# UART-FTDI-USB.net
KiCad netlist of a schematic drawn in Altium Designer
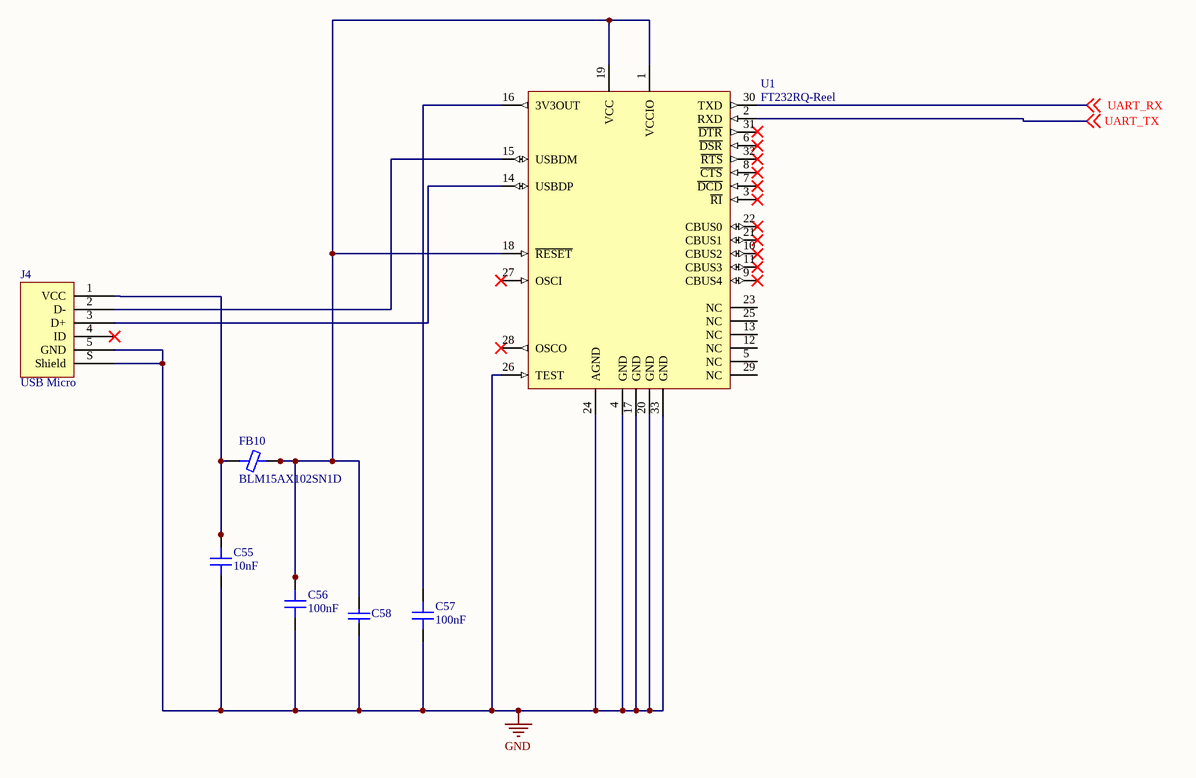
[diagram p0: UART-FTDI-USB.SchDoc]

(export (version "E")
  (design (tool "Eeschema 10.0.6"))
  (components
    (comp (ref "C55")
      (value "10nF")
      (footprint "CAP 0402/1005")
      (description "TAIYO YUDEN - TMK105B7103KV-F - CERAMIC CAPACITOR 0.01UF, 25V, X7R, 10%, 0402, FULL REEL")
      (fields (field (name "TOLERANCE") "10%") (field (name "VOLTAGE") "25V"))
      (libsource (lib "SCH - PASSIVES - CAPACITOR") (part "Capacitor"))
    )
    (comp (ref "C56")
      (value "100nF")
      (footprint "CAP 0402/1005")
      (description "Cap Ceramic 0.1uF 10V X5R 20% Pad SMD 0402 85C T/R")
      (fields (field (name "TOLERANCE") "20%"))
      (libsource (lib "SCH - PASSIVES - CAPACITOR") (part "Capacitor"))
    )
    (comp (ref "C57")
      (value "100nF")
      (footprint "CAP 0402/1005")
      (description "Cap Ceramic 0.1uF 10V X5R 20% Pad SMD 0402 85C T/R")
      (fields (field (name "TOLERANCE") "20%"))
      (libsource (lib "SCH - PASSIVES - CAPACITOR") (part "Capacitor"))
    )
    (comp (ref "C58")
      (value "GRM155R60J475ME47D")
      (footprint "CAPC1005X55X25NL05T10")
      (fields (field (name "MANUFACTURER") "Murata"))
      (libsource (lib "Altium Content Vault") (part "CAP"))
    )
    (comp (ref "FB10")
      (value "BLM15AX102SN1D")
      (footprint "FER 0402/1005")
      (description "Ferrite Beads Multi-Layer 1KOhm 25% 100MHz 350mA 490mOhm DCR 0402 T/R")
      (fields (field (name "TOLERANCE") "25%"))
      (libsource (lib "SCH - PASSIVES - FERRITE CHIP") (part "Ferrite Chip"))
    )
    (comp (ref "J4")
      (value "USB Micro")
      (footprint "FCI USB 10118193-0001LF")
      (description "CONN RCPT USB2.0 MICRO B SMD R/A")
      (libsource (lib "SCH - CONNECTORS - USB 2.0 TYPE B MICRO") (part "USB 2.0 Type B Micro"))
    )
    (comp (ref "U1")
      (value "FT232RQ-Reel")
      (footprint "PQFN5X5-32_V")
      (description "USB UART Asynchronous Serial Data Transfer Chip, 32-pin QFN, Tape and Reel")
      (fields (field (name "MANUFACTURER") "FTDI"))
      (libsource (lib "Altium Content Vault") (part "COM-UART-FT232R-SQ32"))
    )
  )
  (nets
    (net (code "1") (name "GND") (class "Default")
      (node (ref "C55") (pin "1") (pinfunction "1_1") (pintype "passive"))
      (node (ref "C56") (pin "1") (pinfunction "1_1") (pintype "passive"))
      (node (ref "C57") (pin "1") (pinfunction "1_1") (pintype "passive"))
      (node (ref "C58") (pin "1") (pinfunction "1_1") (pintype "passive"))
      (node (ref "J4") (pin "5") (pinfunction "GND_5") (pintype "passive"))
      (node (ref "J4") (pin "S") (pinfunction "Shield_S") (pintype "passive"))
      (node (ref "U1") (pin "17") (pinfunction "GND_17") (pintype "power_in"))
      (node (ref "U1") (pin "20") (pinfunction "GND_20") (pintype "power_in"))
      (node (ref "U1") (pin "24") (pinfunction "AGND_24") (pintype "power_in"))
      (node (ref "U1") (pin "26") (pinfunction "TEST_26") (pintype "input"))
      (node (ref "U1") (pin "33") (pinfunction "GND_33") (pintype "power_in"))
      (node (ref "U1") (pin "4") (pinfunction "GND_4") (pintype "power_in"))
    )
    (net (code "2") (name "Net-(J4-D+)") (class "Default")
      (node (ref "J4") (pin "3") (pinfunction "D+_3") (pintype "passive"))
      (node (ref "U1") (pin "14") (pinfunction "USBDP_14") (pintype "bidirectional"))
    )
    (net (code "3") (name "Net-(J4-D-)") (class "Default")
      (node (ref "J4") (pin "2") (pinfunction "D-_2") (pintype "passive"))
      (node (ref "U1") (pin "15") (pinfunction "USBDM_15") (pintype "bidirectional"))
    )
    (net (code "4") (name "Net-(J4-VCC)") (class "Default")
      (node (ref "C55") (pin "2") (pinfunction "2_2") (pintype "passive"))
      (node (ref "FB10") (pin "2") (pinfunction "2_2") (pintype "passive"))
      (node (ref "J4") (pin "1") (pinfunction "VCC_1") (pintype "passive"))
    )
    (net (code "5") (name "Net-(U1-3V3OUT)") (class "Default")
      (node (ref "C57") (pin "2") (pinfunction "2_2") (pintype "passive"))
      (node (ref "U1") (pin "16") (pinfunction "3V3OUT_16") (pintype "output"))
    )
    (net (code "6") (name "Net-(U1-VCC)") (class "Default")
      (node (ref "C56") (pin "2") (pinfunction "2_2") (pintype "passive"))
      (node (ref "C58") (pin "2") (pinfunction "2_2") (pintype "passive"))
      (node (ref "FB10") (pin "1") (pinfunction "1_1") (pintype "passive"))
      (node (ref "U1") (pin "1") (pinfunction "VCCIO_1") (pintype "power_in"))
      (node (ref "U1") (pin "18") (pinfunction "~{RESET}_18") (pintype "input"))
      (node (ref "U1") (pin "19") (pinfunction "VCC_19") (pintype "power_in"))
    )
    (net (code "7") (name "UART_RX") (class "Default")
      (node (ref "U1") (pin "30") (pinfunction "TXD_30") (pintype "output"))
    )
    (net (code "8") (name "UART_TX") (class "Default")
      (node (ref "U1") (pin "2") (pinfunction "RXD_2") (pintype "input"))
    )
    (net (code "9") (name "unconnected-(J4-ID-Pad4)") (class "Default")
      (node (ref "J4") (pin "4") (pinfunction "ID_4") (pintype "passive+no_connect"))
    )
    (net (code "10") (name "unconnected-(U1-CBUS0-Pad22)") (class "Default")
      (node (ref "U1") (pin "22") (pinfunction "CBUS0_22") (pintype "bidirectional+no_connect"))
    )
    (net (code "11") (name "unconnected-(U1-CBUS1-Pad21)") (class "Default")
      (node (ref "U1") (pin "21") (pinfunction "CBUS1_21") (pintype "bidirectional+no_connect"))
    )
    (net (code "12") (name "unconnected-(U1-CBUS2-Pad10)") (class "Default")
      (node (ref "U1") (pin "10") (pinfunction "CBUS2_10") (pintype "bidirectional"))
    )
    (net (code "13") (name "unconnected-(U1-CBUS3-Pad11)") (class "Default")
      (node (ref "U1") (pin "11") (pinfunction "CBUS3_11") (pintype "bidirectional+no_connect"))
    )
    (net (code "14") (name "unconnected-(U1-CBUS4-Pad9)") (class "Default")
      (node (ref "U1") (pin "9") (pinfunction "CBUS4_9") (pintype "bidirectional+no_connect"))
    )
    (net (code "15") (name "unconnected-(U1-NC-Pad5)") (class "Default")
      (node (ref "U1") (pin "5") (pinfunction "NC_5") (pintype "passive"))
    )
    (net (code "16") (name "unconnected-(U1-NC-Pad12)") (class "Default")
      (node (ref "U1") (pin "12") (pinfunction "NC_12") (pintype "passive"))
    )
    (net (code "17") (name "unconnected-(U1-NC-Pad13)") (class "Default")
      (node (ref "U1") (pin "13") (pinfunction "NC_13") (pintype "passive"))
    )
    (net (code "18") (name "unconnected-(U1-NC-Pad23)") (class "Default")
      (node (ref "U1") (pin "23") (pinfunction "NC_23") (pintype "passive"))
    )
    (net (code "19") (name "unconnected-(U1-NC-Pad25)") (class "Default")
      (node (ref "U1") (pin "25") (pinfunction "NC_25") (pintype "passive"))
    )
    (net (code "20") (name "unconnected-(U1-NC-Pad29)") (class "Default")
      (node (ref "U1") (pin "29") (pinfunction "NC_29") (pintype "passive"))
    )
    (net (code "21") (name "unconnected-(U1-OSCI-Pad27)") (class "Default")
      (node (ref "U1") (pin "27") (pinfunction "OSCI_27") (pintype "input+no_connect"))
    )
    (net (code "22") (name "unconnected-(U1-OSCO-Pad28)") (class "Default")
      (node (ref "U1") (pin "28") (pinfunction "OSCO_28") (pintype "output+no_connect"))
    )
    (net (code "23") (name "unconnected-(U1-~{CTS}-Pad8)") (class "Default")
      (node (ref "U1") (pin "8") (pinfunction "~{CTS}_8") (pintype "input+no_connect"))
    )
    (net (code "24") (name "unconnected-(U1-~{DCD}-Pad7)") (class "Default")
      (node (ref "U1") (pin "7") (pinfunction "~{DCD}_7") (pintype "input+no_connect"))
    )
    (net (code "25") (name "unconnected-(U1-~{DSR}-Pad6)") (class "Default")
      (node (ref "U1") (pin "6") (pinfunction "~{DSR}_6") (pintype "input+no_connect"))
    )
    (net (code "26") (name "unconnected-(U1-~{DTR}-Pad31)") (class "Default")
      (node (ref "U1") (pin "31") (pinfunction "~{DTR}_31") (pintype "output"))
    )
    (net (code "27") (name "unconnected-(U1-~{RI}-Pad3)") (class "Default")
      (node (ref "U1") (pin "3") (pinfunction "~{RI}_3") (pintype "input+no_connect"))
    )
    (net (code "28") (name "unconnected-(U1-~{RTS}-Pad32)") (class "Default")
      (node (ref "U1") (pin "32") (pinfunction "~{RTS}_32") (pintype "output+no_connect"))
    )
  )
)
